# ESP32_with_USBC.net
KiCad netlist of a schematic drawn in Altium Designer
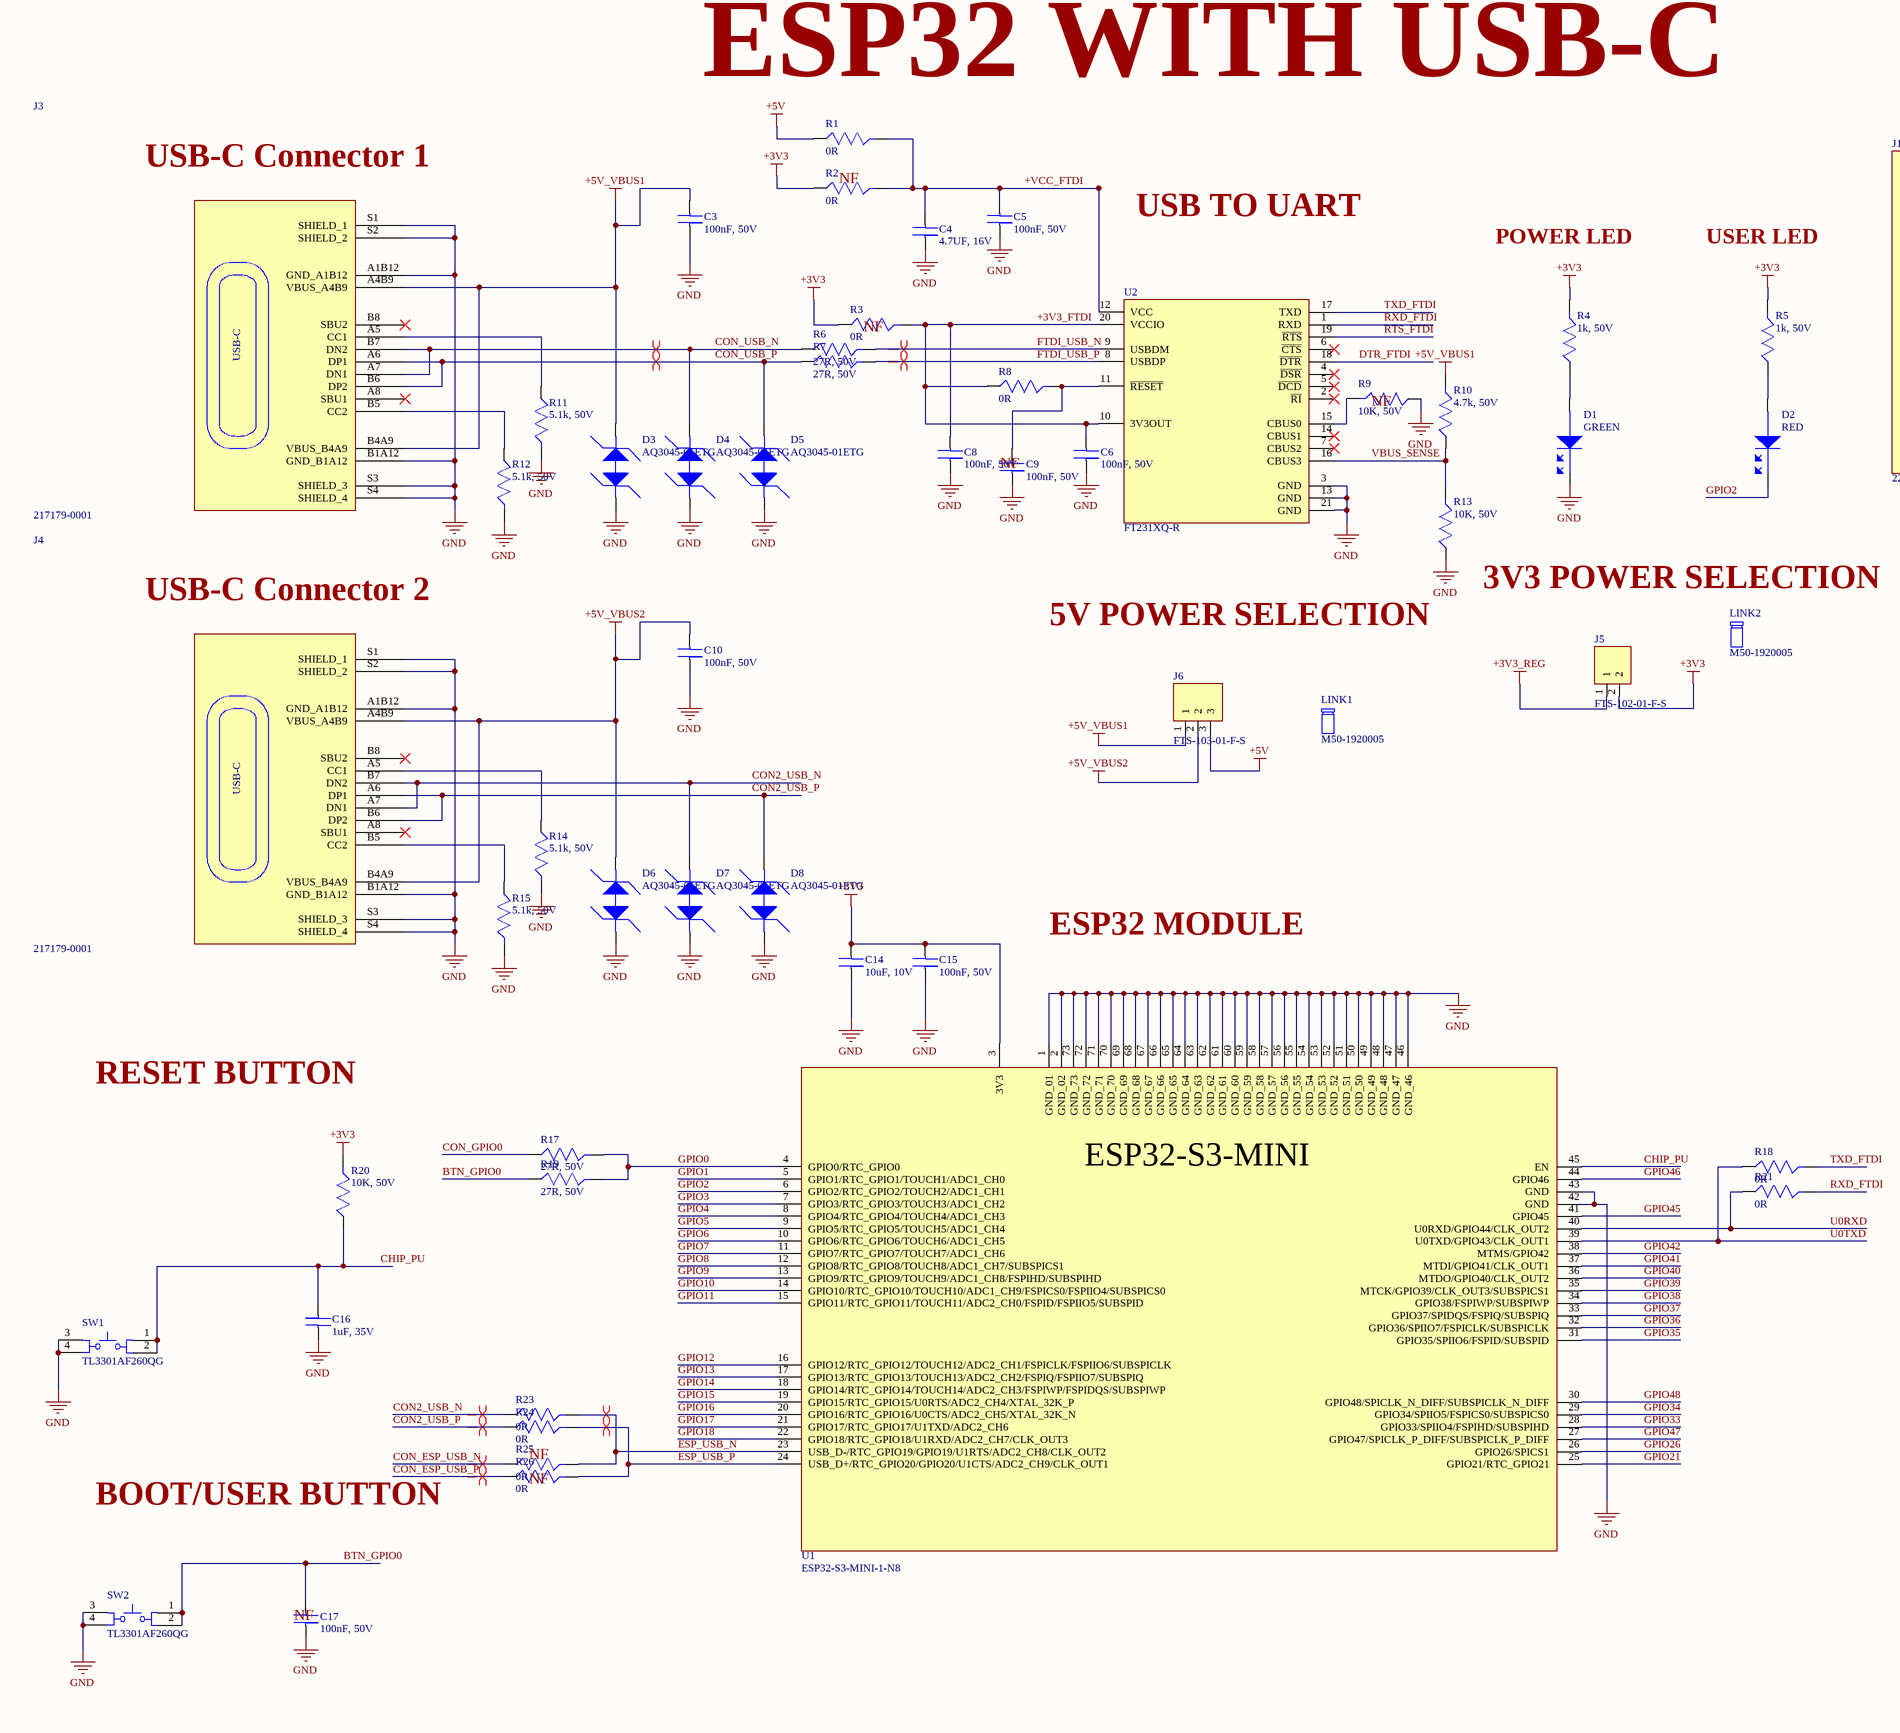
[diagram p0: ESP32 with USBC.SchDoc, left]
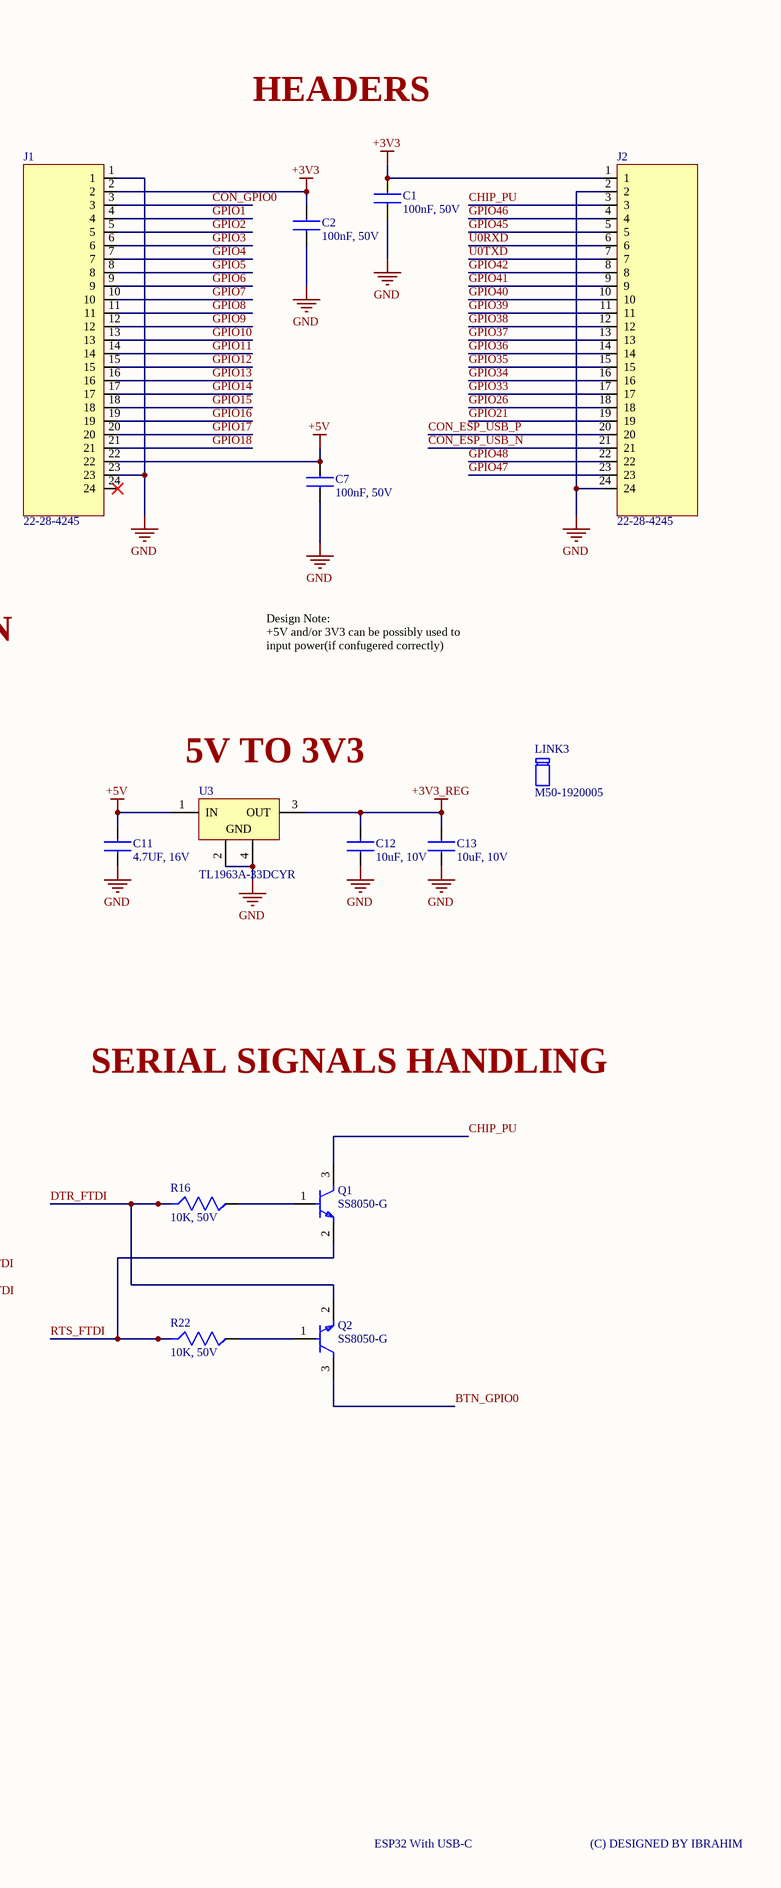
[diagram p1: ESP32 with USBC.SchDoc, right]

(export (version "E")
  (design (tool "Eeschema 10.0.6"))
  (components
    (comp (ref "C1")
      (value "100nF, 50V")
      (footprint "CAPC1005X65N")
      (description "CAP CER 0.1UF 50V X7R 0402")
      (fields
        (field (name "MANUFACTURER") "Samsung Electro-Mechanics")
        (field (name "MANUFACTURER PART NUMBER") "CL05B104KB54PNC")
      )
      (libsource (lib "Schlib") (part "CL05B104KB54PNC"))
    )
    (comp (ref "C2")
      (value "100nF, 50V")
      (footprint "CAPC1005X65N")
      (description "CAP CER 0.1UF 50V X7R 0402")
      (fields
        (field (name "MANUFACTURER") "Samsung Electro-Mechanics")
        (field (name "MANUFACTURER PART NUMBER") "CL05B104KB54PNC")
      )
      (libsource (lib "Schlib") (part "CL05B104KB54PNC"))
    )
    (comp (ref "C3")
      (value "100nF, 50V")
      (footprint "CAPC1005X65N")
      (description "CAP CER 0.1UF 50V X7R 0402")
      (fields
        (field (name "MANUFACTURER") "Samsung Electro-Mechanics")
        (field (name "MANUFACTURER PART NUMBER") "CL05B104KB54PNC")
      )
      (libsource (lib "Schlib") (part "CL05B104KB54PNC"))
    )
    (comp (ref "C4")
      (value "4.7UF, 16V")
      (footprint "CAPC1005X65N")
      (description "CAP CER 4.7UF 16V X5R 0402")
      (fields (field (name "TOLERANCE") "20%") (field (name "LCSC PART NUMBER") "C318563"))
      (libsource (lib "Schlib") (part "CMP-13271-001468-1"))
    )
    (comp (ref "C5")
      (value "100nF, 50V")
      (footprint "CAPC1005X65N")
      (description "CAP CER 0.1UF 50V X7R 0402")
      (fields
        (field (name "MANUFACTURER") "Samsung Electro-Mechanics")
        (field (name "MANUFACTURER PART NUMBER") "CL05B104KB54PNC")
      )
      (libsource (lib "Schlib") (part "CL05B104KB54PNC"))
    )
    (comp (ref "C6")
      (value "100nF, 50V")
      (footprint "CAPC1005X65N")
      (description "CAP CER 0.1UF 50V X7R 0402")
      (fields
        (field (name "MANUFACTURER") "Samsung Electro-Mechanics")
        (field (name "MANUFACTURER PART NUMBER") "CL05B104KB54PNC")
      )
      (libsource (lib "Schlib") (part "CL05B104KB54PNC"))
    )
    (comp (ref "C7")
      (value "100nF, 50V")
      (footprint "CAPC1005X65N")
      (description "CAP CER 0.1UF 50V X7R 0402")
      (fields
        (field (name "MANUFACTURER") "Samsung Electro-Mechanics")
        (field (name "MANUFACTURER PART NUMBER") "CL05B104KB54PNC")
      )
      (libsource (lib "Schlib") (part "CL05B104KB54PNC"))
    )
    (comp (ref "C8")
      (value "100nF, 50V")
      (footprint "CAPC1005X65N")
      (description "CAP CER 0.1UF 50V X7R 0402")
      (fields
        (field (name "MANUFACTURER") "Samsung Electro-Mechanics")
        (field (name "MANUFACTURER PART NUMBER") "CL05B104KB54PNC")
      )
      (libsource (lib "Schlib") (part "CL05B104KB54PNC"))
    )
    (comp (ref "C9")
      (value "100nF, 50V")
      (footprint "CAPC1005X65N")
      (description "CAP CER 0.1UF 50V X7R 0402")
      (fields
        (field (name "MANUFACTURER") "Samsung Electro-Mechanics")
        (field (name "MANUFACTURER PART NUMBER") "CL05B104KB54PNC")
      )
      (libsource (lib "Schlib") (part "CL05B104KB54PNC"))
    )
    (comp (ref "C10")
      (value "100nF, 50V")
      (footprint "CAPC1005X65N")
      (description "CAP CER 0.1UF 50V X7R 0402")
      (fields
        (field (name "MANUFACTURER") "Samsung Electro-Mechanics")
        (field (name "MANUFACTURER PART NUMBER") "CL05B104KB54PNC")
      )
      (libsource (lib "Schlib") (part "CL05B104KB54PNC"))
    )
    (comp (ref "C11")
      (value "4.7UF, 16V")
      (footprint "CAPC1005X65N")
      (description "CAP CER 4.7UF 16V X5R 0402")
      (fields (field (name "TOLERANCE") "20%") (field (name "LCSC PART NUMBER") "C318563"))
      (libsource (lib "Schlib") (part "CMP-13271-001468-1"))
    )
    (comp (ref "C12")
      (value "10uF, 10V")
      (footprint "CAPC1005X65N")
      (description "CAP CER 10UF 10V X5R 0402")
      (fields
        (field (name "MANUFACTURER") "Samsung Electro-Mechanics")
        (field (name "MANUFACTURER PART NUMBER") "CL05A106MP8NUB8")
      )
      (libsource (lib "Schlib") (part "CL05A106MP8NUB8"))
    )
    (comp (ref "C13")
      (value "10uF, 10V")
      (footprint "CAPC1005X65N")
      (description "CAP CER 10UF 10V X5R 0402")
      (fields
        (field (name "MANUFACTURER") "Samsung Electro-Mechanics")
        (field (name "MANUFACTURER PART NUMBER") "CL05A106MP8NUB8")
      )
      (libsource (lib "Schlib") (part "CL05A106MP8NUB8"))
    )
    (comp (ref "C14")
      (value "10uF, 10V")
      (footprint "CAPC1005X65N")
      (description "CAP CER 10UF 10V X5R 0402")
      (fields
        (field (name "MANUFACTURER") "Samsung Electro-Mechanics")
        (field (name "MANUFACTURER PART NUMBER") "CL05A106MP8NUB8")
      )
      (libsource (lib "Schlib") (part "CL05A106MP8NUB8"))
    )
    (comp (ref "C15")
      (value "100nF, 50V")
      (footprint "CAPC1005X65N")
      (description "CAP CER 0.1UF 50V X7R 0402")
      (fields
        (field (name "MANUFACTURER") "Samsung Electro-Mechanics")
        (field (name "MANUFACTURER PART NUMBER") "CL05B104KB54PNC")
      )
      (libsource (lib "Schlib") (part "CL05B104KB54PNC"))
    )
    (comp (ref "C16")
      (value "1uF, 35V")
      (footprint "CAPC1005X65N")
      (description "CAP CER 1UF 35V X5R 0402")
      (fields
        (field (name "MANUFACTURER") "Samsung Electro-Mechanics")
        (field (name "MANUFACTURER PART NUMBER") "CL05A105KL5NRNC")
      )
      (libsource (lib "Schlib") (part "CL05A105KL5NRNC"))
    )
    (comp (ref "C17")
      (value "100nF, 50V")
      (footprint "CAPC1005X65N")
      (description "CAP CER 0.1UF 50V X7R 0402")
      (fields
        (field (name "MANUFACTURER") "Samsung Electro-Mechanics")
        (field (name "MANUFACTURER PART NUMBER") "CL05B104KB54PNC")
      )
      (libsource (lib "Schlib") (part "CL05B104KB54PNC"))
    )
    (comp (ref "D1")
      (value "GREEN")
      (footprint "LED0402G")
      (description "LED YLW-GRN 0402 SMD")
      (fields
        (field (name "MANUFACTURER") "Vishay")
        (field (name "MANUFACTURER PART NUMBER") "VLMG1500-GS08")
      )
      (libsource (lib "Schlib") (part "VLMG1500-GS08"))
    )
    (comp (ref "D2")
      (value "RED")
      (footprint "LED0402R")
      (description "LED RED 0402 SMD")
      (fields
        (field (name "MANUFACTURER") "Vishay")
        (field (name "MANUFACTURER PART NUMBER") "VLMS1500-GS08")
      )
      (libsource (lib "Schlib") (part "VLMS1500-GS08"))
    )
    (comp (ref "D3")
      (value "AQ3045-01ETG")
      (footprint "SOD882")
      (description "TVS DIODE 5.3VWM 12VC SOD882")
      (fields (field (name "MANUFACTURER") "Littelfuse") (field (name "LCSC PART NUMBER") "C3710326"))
      (libsource (lib "Schlib") (part "AQ3045-01ETG"))
    )
    (comp (ref "D4")
      (value "AQ3045-01ETG")
      (footprint "SOD882")
      (description "TVS DIODE 5.3VWM 12VC SOD882")
      (fields (field (name "MANUFACTURER") "Littelfuse") (field (name "LCSC PART NUMBER") "C3710326"))
      (libsource (lib "Schlib") (part "AQ3045-01ETG"))
    )
    (comp (ref "D5")
      (value "AQ3045-01ETG")
      (footprint "SOD882")
      (description "TVS DIODE 5.3VWM 12VC SOD882")
      (fields (field (name "MANUFACTURER") "Littelfuse") (field (name "LCSC PART NUMBER") "C3710326"))
      (libsource (lib "Schlib") (part "AQ3045-01ETG"))
    )
    (comp (ref "D6")
      (value "AQ3045-01ETG")
      (footprint "SOD882")
      (description "TVS DIODE 5.3VWM 12VC SOD882")
      (fields (field (name "MANUFACTURER") "Littelfuse") (field (name "LCSC PART NUMBER") "C3710326"))
      (libsource (lib "Schlib") (part "AQ3045-01ETG"))
    )
    (comp (ref "D7")
      (value "AQ3045-01ETG")
      (footprint "SOD882")
      (description "TVS DIODE 5.3VWM 12VC SOD882")
      (fields (field (name "MANUFACTURER") "Littelfuse") (field (name "LCSC PART NUMBER") "C3710326"))
      (libsource (lib "Schlib") (part "AQ3045-01ETG"))
    )
    (comp (ref "D8")
      (value "AQ3045-01ETG")
      (footprint "SOD882")
      (description "TVS DIODE 5.3VWM 12VC SOD882")
      (fields (field (name "MANUFACTURER") "Littelfuse") (field (name "LCSC PART NUMBER") "C3710326"))
      (libsource (lib "Schlib") (part "AQ3045-01ETG"))
    )
    (comp (ref "J1")
      (value "22-28-4245")
      (footprint "HDR_1X24_2.54MM")
      (description "Conn Unshrouded Header HDR 24 POS 2.54mm Solder ST Thru-Hole KK® Bag")
      (fields (field (name "MANUFACTURER") "Molex") (field (name "LCSC PART NUMBER") "C7145888"))
      (libsource (lib "Schlib") (part "22-28-4245"))
    )
    (comp (ref "J2")
      (value "22-28-4245")
      (footprint "HDR_1X24_2.54MM")
      (description "Conn Unshrouded Header HDR 24 POS 2.54mm Solder ST Thru-Hole KK® Bag")
      (fields (field (name "MANUFACTURER") "Molex") (field (name "LCSC PART NUMBER") "C7145888"))
      (libsource (lib "") (part "22-28-4245_1"))
    )
    (comp (ref "J3")
      (value "217179-0001")
      (footprint "FP-2171790001-MFG")
      (description "CONN RCP USB2.0 TYP C 24P SMD RA")
      (fields (field (name "MANUFACTURER") "Molex") (field (name "LCSC PART NUMBER") "C3197684"))
      (libsource (lib "Schlib") (part "217179-0001"))
    )
    (comp (ref "J4")
      (value "217179-0001")
      (footprint "FP-2171790001-MFG")
      (description "CONN RCP USB2.0 TYP C 24P SMD RA")
      (fields (field (name "MANUFACTURER") "Molex") (field (name "LCSC PART NUMBER") "C3197684"))
      (libsource (lib "Schlib") (part "217179-0001"))
    )
    (comp (ref "J5")
      (value "FTS-102-01-F-S")
      (footprint "HDR_1X2_1.27MM")
      (description "CONN HEADER VERT 2POS 1.27MM")
      (fields (field (name "MANUFACTURER") "Samtec") (field (name "LCSC PART NUMBER") "C6045317"))
      (libsource (lib "Schlib") (part "FTS-102-01-F-S"))
    )
    (comp (ref "J6")
      (value "FTS-103-01-F-S")
      (footprint "HDR_1X3_1.27MM")
      (description "CONN HEADER VERT 3POS 1.27MM")
      (fields (field (name "MANUFACTURER") "Samtec") (field (name "LCSC PART NUMBER") "C3333578"))
      (libsource (lib "Schlib") (part "FTS-103-01-F-S"))
    )
    (comp (ref "LINK1")
      (value "M50-1920005")
      (description "CONN SHUNT 1.27MM RED")
      (fields (field (name "MANUFACTURER") "Harwin") (field (name "LCSC PART NUMBER") "C6985646"))
      (libsource (lib "Schlib") (part "M50-1920005"))
    )
    (comp (ref "LINK2")
      (value "M50-1920005")
      (description "CONN SHUNT 1.27MM RED")
      (fields (field (name "MANUFACTURER") "Harwin") (field (name "LCSC PART NUMBER") "C6985646"))
      (libsource (lib "Schlib") (part "M50-1920005"))
    )
    (comp (ref "LINK3")
      (value "M50-1920005")
      (description "CONN SHUNT 1.27MM RED")
      (fields (field (name "MANUFACTURER") "Harwin") (field (name "LCSC PART NUMBER") "C6985646"))
      (libsource (lib "Schlib") (part "M50-1920005"))
    )
    (comp (ref "Q1")
      (value "SS8050-G")
      (footprint "FP-SS8050-G-IPC_B")
      (description "TRANS NPN 25V 1.5A SOT-23-3")
      (fields (field (name "MANUFACTURER") "Comchip") (field (name "LCSC PART NUMBER") "C3199946"))
      (libsource (lib "Schlib") (part "SS8050-G"))
    )
    (comp (ref "Q2")
      (value "SS8050-G")
      (footprint "FP-SS8050-G-IPC_B")
      (description "TRANS NPN 25V 1.5A SOT-23-3")
      (fields (field (name "MANUFACTURER") "Comchip") (field (name "LCSC PART NUMBER") "C3199946"))
      (libsource (lib "Schlib") (part "SS8050-G"))
    )
    (comp (ref "R1")
      (value "0R")
      (footprint "RESC1005X37N")
      (description "RES 0 OHM JUMPER 1/16W 0402")
      (fields
        (field (name "MANUFACTURER") "Yageo Group")
        (field (name "MANUFACTURER PART NUMBER") "RC0402JR-070RL")
      )
      (libsource (lib "Schlib") (part "RC0402JR-070RL"))
    )
    (comp (ref "R2")
      (value "0R")
      (footprint "RESC1005X37N")
      (description "RES 0 OHM JUMPER 1/16W 0402")
      (fields
        (field (name "MANUFACTURER") "Yageo Group")
        (field (name "MANUFACTURER PART NUMBER") "RC0402JR-070RL")
      )
      (libsource (lib "Schlib") (part "RC0402JR-070RL"))
    )
    (comp (ref "R3")
      (value "0R")
      (footprint "RESC1005X37N")
      (description "RES 0 OHM JUMPER 1/16W 0402")
      (fields
        (field (name "MANUFACTURER") "Yageo Group")
        (field (name "MANUFACTURER PART NUMBER") "RC0402JR-070RL")
      )
      (libsource (lib "Schlib") (part "RC0402JR-070RL"))
    )
    (comp (ref "R4")
      (value "1k, 50V")
      (footprint "RESC1005X37N")
      (description "RES 1K OHM 1% 1/16W 0402")
      (fields
        (field (name "MANUFACTURER") "Yageo Group")
        (field (name "MANUFACTURER PART NUMBER") "RC0402FR-071KL")
      )
      (libsource (lib "Schlib") (part "RC0402FR-071KL"))
    )
    (comp (ref "R5")
      (value "1k, 50V")
      (footprint "RESC1005X37N")
      (description "RES 1K OHM 1% 1/16W 0402")
      (fields
        (field (name "MANUFACTURER") "Yageo Group")
        (field (name "MANUFACTURER PART NUMBER") "RC0402FR-071KL")
      )
      (libsource (lib "Schlib") (part "RC0402FR-071KL"))
    )
    (comp (ref "R6")
      (value "27R, 50V")
      (footprint "RESC1005X37N")
      (description "RES 27 OHM 1% 1/16W 0402")
      (fields
        (field (name "MANUFACTURER") "Yageo Group")
        (field (name "MANUFACTURER PART NUMBER") "RC0402FR-0727RL")
      )
      (libsource (lib "Schlib") (part "RC0402FR-0727RL"))
    )
    (comp (ref "R7")
      (value "27R, 50V")
      (footprint "RESC1005X37N")
      (description "RES 27 OHM 1% 1/16W 0402")
      (fields
        (field (name "MANUFACTURER") "Yageo Group")
        (field (name "MANUFACTURER PART NUMBER") "RC0402FR-0727RL")
      )
      (libsource (lib "Schlib") (part "RC0402FR-0727RL"))
    )
    (comp (ref "R8")
      (value "0R")
      (footprint "RESC1005X37N")
      (description "RES 0 OHM JUMPER 1/16W 0402")
      (fields
        (field (name "MANUFACTURER") "Yageo Group")
        (field (name "MANUFACTURER PART NUMBER") "RC0402JR-070RL")
      )
      (libsource (lib "Schlib") (part "RC0402JR-070RL"))
    )
    (comp (ref "R9")
      (value "10K, 50V")
      (footprint "RESC1005X37N")
      (description "RES SMD 10K OHM 1% 1/16W 0402")
      (fields
        (field (name "MANUFACTURER") "Yageo Group")
        (field (name "MANUFACTURER PART NUMBER") "AC0402FR-0710KL")
      )
      (libsource (lib "Schlib") (part "AC0402FR-0710KL"))
    )
    (comp (ref "R10")
      (value "4.7k, 50V")
      (footprint "RESC1005X37N")
      (description "RES 4.7K OHM 1% 1/16W 0402")
      (fields
        (field (name "MANUFACTURER") "Yageo Group")
        (field (name "MANUFACTURER PART NUMBER") "RC0402FR-074K7L")
      )
      (libsource (lib "Schlib") (part "RC0402FR-074K7L"))
    )
    (comp (ref "R11")
      (value "5.1k, 50V")
      (footprint "RESC1005X37N")
      (description "Res Thick Film 0402 5.1K Ohm 1% 0.063W(1/16W) ±100ppm/C Pad SMD Automotive T/R")
      (fields
        (field (name "MANUFACTURER") "Yageo Group")
        (field (name "MANUFACTURER PART NUMBER") "AC0402FR-075K1L")
      )
      (libsource (lib "Schlib") (part "AC0402FR-075K1L"))
    )
    (comp (ref "R12")
      (value "5.1k, 50V")
      (footprint "RESC1005X37N")
      (description "Res Thick Film 0402 5.1K Ohm 1% 0.063W(1/16W) ±100ppm/C Pad SMD Automotive T/R")
      (fields
        (field (name "MANUFACTURER") "Yageo Group")
        (field (name "MANUFACTURER PART NUMBER") "AC0402FR-075K1L")
      )
      (libsource (lib "Schlib") (part "AC0402FR-075K1L"))
    )
    (comp (ref "R13")
      (value "10K, 50V")
      (footprint "RESC1005X37N")
      (description "RES SMD 10K OHM 1% 1/16W 0402")
      (fields
        (field (name "MANUFACTURER") "Yageo Group")
        (field (name "MANUFACTURER PART NUMBER") "AC0402FR-0710KL")
      )
      (libsource (lib "Schlib") (part "AC0402FR-0710KL"))
    )
    (comp (ref "R14")
      (value "5.1k, 50V")
      (footprint "RESC1005X37N")
      (description "Res Thick Film 0402 5.1K Ohm 1% 0.063W(1/16W) ±100ppm/C Pad SMD Automotive T/R")
      (fields
        (field (name "MANUFACTURER") "Yageo Group")
        (field (name "MANUFACTURER PART NUMBER") "AC0402FR-075K1L")
      )
      (libsource (lib "Schlib") (part "AC0402FR-075K1L"))
    )
    (comp (ref "R15")
      (value "5.1k, 50V")
      (footprint "RESC1005X37N")
      (description "Res Thick Film 0402 5.1K Ohm 1% 0.063W(1/16W) ±100ppm/C Pad SMD Automotive T/R")
      (fields
        (field (name "MANUFACTURER") "Yageo Group")
        (field (name "MANUFACTURER PART NUMBER") "AC0402FR-075K1L")
      )
      (libsource (lib "Schlib") (part "AC0402FR-075K1L"))
    )
    (comp (ref "R16")
      (value "10K, 50V")
      (footprint "RESC1005X37N")
      (description "RES SMD 10K OHM 1% 1/16W 0402")
      (fields
        (field (name "MANUFACTURER") "Yageo Group")
        (field (name "MANUFACTURER PART NUMBER") "AC0402FR-0710KL")
      )
      (libsource (lib "Schlib") (part "AC0402FR-0710KL"))
    )
    (comp (ref "R17")
      (value "27R, 50V")
      (footprint "RESC1005X37N")
      (description "RES 27 OHM 1% 1/16W 0402")
      (fields
        (field (name "MANUFACTURER") "Yageo Group")
        (field (name "MANUFACTURER PART NUMBER") "RC0402FR-0727RL")
      )
      (libsource (lib "Schlib") (part "RC0402FR-0727RL"))
    )
    (comp (ref "R18")
      (value "0R")
      (footprint "RESC1005X37N")
      (description "RES 0 OHM JUMPER 1/16W 0402")
      (fields
        (field (name "MANUFACTURER") "Yageo Group")
        (field (name "MANUFACTURER PART NUMBER") "RC0402JR-070RL")
      )
      (libsource (lib "Schlib") (part "RC0402JR-070RL"))
    )
    (comp (ref "R19")
      (value "27R, 50V")
      (footprint "RESC1005X37N")
      (description "RES 27 OHM 1% 1/16W 0402")
      (fields
        (field (name "MANUFACTURER") "Yageo Group")
        (field (name "MANUFACTURER PART NUMBER") "RC0402FR-0727RL")
      )
      (libsource (lib "Schlib") (part "RC0402FR-0727RL"))
    )
    (comp (ref "R20")
      (value "10K, 50V")
      (footprint "RESC1005X37N")
      (description "RES SMD 10K OHM 1% 1/16W 0402")
      (fields
        (field (name "MANUFACTURER") "Yageo Group")
        (field (name "MANUFACTURER PART NUMBER") "AC0402FR-0710KL")
      )
      (libsource (lib "Schlib") (part "AC0402FR-0710KL"))
    )
    (comp (ref "R21")
      (value "0R")
      (footprint "RESC1005X37N")
      (description "RES 0 OHM JUMPER 1/16W 0402")
      (fields
        (field (name "MANUFACTURER") "Yageo Group")
        (field (name "MANUFACTURER PART NUMBER") "RC0402JR-070RL")
      )
      (libsource (lib "Schlib") (part "RC0402JR-070RL"))
    )
    (comp (ref "R22")
      (value "10K, 50V")
      (footprint "RESC1005X37N")
      (description "RES SMD 10K OHM 1% 1/16W 0402")
      (fields
        (field (name "MANUFACTURER") "Yageo Group")
        (field (name "MANUFACTURER PART NUMBER") "AC0402FR-0710KL")
      )
      (libsource (lib "Schlib") (part "AC0402FR-0710KL"))
    )
    (comp (ref "R23")
      (value "0R")
      (footprint "RESC1005X37N")
      (description "RES 0 OHM JUMPER 1/16W 0402")
      (fields
        (field (name "MANUFACTURER") "Yageo Group")
        (field (name "MANUFACTURER PART NUMBER") "RC0402JR-070RL")
      )
      (libsource (lib "Schlib") (part "RC0402JR-070RL"))
    )
    (comp (ref "R24")
      (value "0R")
      (footprint "RESC1005X37N")
      (description "RES 0 OHM JUMPER 1/16W 0402")
      (fields
        (field (name "MANUFACTURER") "Yageo Group")
        (field (name "MANUFACTURER PART NUMBER") "RC0402JR-070RL")
      )
      (libsource (lib "Schlib") (part "RC0402JR-070RL"))
    )
    (comp (ref "R25")
      (value "0R")
      (footprint "RESC1005X37N")
      (description "RES 0 OHM JUMPER 1/16W 0402")
      (fields
        (field (name "MANUFACTURER") "Yageo Group")
        (field (name "MANUFACTURER PART NUMBER") "RC0402JR-070RL")
      )
      (libsource (lib "Schlib") (part "RC0402JR-070RL"))
    )
    (comp (ref "R26")
      (value "0R")
      (footprint "RESC1005X37N")
      (description "RES 0 OHM JUMPER 1/16W 0402")
      (fields
        (field (name "MANUFACTURER") "Yageo Group")
        (field (name "MANUFACTURER PART NUMBER") "RC0402JR-070RL")
      )
      (libsource (lib "Schlib") (part "RC0402JR-070RL"))
    )
    (comp (ref "SW1")
      (value "TL3301AF260QG")
      (footprint "ESWI-TL3301AF260QG_V")
      (description "Switch Tactile N.O. SPST Round Button Gull Wing 0.05A 12VDC 100000Cycles 2.55N SMD T/R")
      (fields (field (name "MANUFACTURER") "E-Switch"))
      (libsource (lib "Schlib") (part "TL3301AF260QG"))
    )
    (comp (ref "SW2")
      (value "TL3301AF260QG")
      (footprint "ESWI-TL3301AF260QG_V")
      (description "Switch Tactile N.O. SPST Round Button Gull Wing 0.05A 12VDC 100000Cycles 2.55N SMD T/R")
      (fields (field (name "MANUFACTURER") "E-Switch"))
      (libsource (lib "Schlib") (part "TL3301AF260QG"))
    )
    (comp (ref "U1")
      (value "ESP32-S3-MINI-1-N8")
      (footprint "XCVR_ESP32-S3-MINI-1-N8")
      (description "20.5dBm ESP32-S3FN8 Chip 2.4GHz SMD WiFi Modules ROHS")
      (fields (field (name "MANUFACTURER") "Espressif Systems") (field (name "LCSC PART NUMBER") "C2913206"))
      (libsource (lib "Schlib") (part "ESP32-S3-MINI-1-N8"))
    )
    (comp (ref "U2")
      (value "FT231XQ-R")
      (footprint "FP-QFN-20-IPC_B")
      (description "IC USB SERIAL FULL UART 20QFN")
      (fields (field (name "MANUFACTURER") "FTDI") (field (name "LCSC PART NUMBER") "C132159"))
      (libsource (lib "Schlib") (part "FT231XQ-R"))
    )
    (comp (ref "U3")
      (value "TL1963A-33DCYR")
      (footprint "DCY0004A_N")
      (description "IC REG LIN 3.3V 1.5A SOT-223-4")
      (fields (field (name "MANUFACTURER") "Texas Instruments") (field (name "LCSC PART NUMBER") "C181262"))
      (libsource (lib "Schlib") (part "TL1963A-33DCYR"))
    )
  )
  (nets
    (net (code "1") (name "+3V3") (class "Default")
      (node (ref "C1") (pin "1") (pinfunction "1_1") (pintype "passive"))
      (node (ref "C14") (pin "1") (pinfunction "1_1") (pintype "passive"))
      (node (ref "C15") (pin "1") (pinfunction "1_1") (pintype "passive"))
      (node (ref "C2") (pin "1") (pinfunction "1_1") (pintype "passive"))
      (node (ref "J1") (pin "2") (pinfunction "2_2") (pintype "passive"))
      (node (ref "J2") (pin "1") (pinfunction "1_1") (pintype "passive"))
      (node (ref "J5") (pin "2") (pinfunction "2_2") (pintype "passive"))
      (node (ref "R2") (pin "1") (pinfunction "1_1") (pintype "passive"))
      (node (ref "R20") (pin "2") (pinfunction "2_2") (pintype "passive"))
      (node (ref "R3") (pin "1") (pinfunction "1_1") (pintype "passive"))
      (node (ref "R4") (pin "2") (pinfunction "2_2") (pintype "passive"))
      (node (ref "R5") (pin "2") (pinfunction "2_2") (pintype "passive"))
      (node (ref "U1") (pin "3") (pinfunction "3V3_3") (pintype "passive"))
    )
    (net (code "2") (name "+3V3_REG") (class "Default")
      (node (ref "C12") (pin "1") (pinfunction "1_1") (pintype "passive"))
      (node (ref "C13") (pin "1") (pinfunction "1_1") (pintype "passive"))
      (node (ref "J5") (pin "1") (pinfunction "1_1") (pintype "passive"))
      (node (ref "U3") (pin "3") (pinfunction "OUT_3") (pintype "power_in"))
    )
    (net (code "3") (name "+5V") (class "Default")
      (node (ref "C11") (pin "1") (pinfunction "1_1") (pintype "passive"))
      (node (ref "C7") (pin "1") (pinfunction "1_1") (pintype "passive"))
      (node (ref "J1") (pin "22") (pinfunction "22_22") (pintype "passive"))
      (node (ref "J6") (pin "3") (pinfunction "3_3") (pintype "passive"))
      (node (ref "R1") (pin "1") (pinfunction "1_1") (pintype "passive"))
      (node (ref "U3") (pin "1") (pinfunction "IN_1") (pintype "power_in"))
    )
    (net (code "4") (name "+5V_VBUS1") (class "Default")
      (node (ref "C3") (pin "1") (pinfunction "1_1") (pintype "passive"))
      (node (ref "D3") (pin "2") (pinfunction "2_2") (pintype "passive"))
      (node (ref "J3") (pin "A4B9") (pinfunction "VBUS_A4B9_A4B9") (pintype "passive"))
      (node (ref "J3") (pin "B4A9") (pinfunction "VBUS_B4A9_B4A9") (pintype "passive"))
      (node (ref "J6") (pin "1") (pinfunction "1_1") (pintype "passive"))
      (node (ref "R10") (pin "2") (pinfunction "2_2") (pintype "passive"))
    )
    (net (code "5") (name "+5V_VBUS2") (class "Default")
      (node (ref "C10") (pin "1") (pinfunction "1_1") (pintype "passive"))
      (node (ref "D6") (pin "2") (pinfunction "2_2") (pintype "passive"))
      (node (ref "J4") (pin "A4B9") (pinfunction "VBUS_A4B9_A4B9") (pintype "passive"))
      (node (ref "J4") (pin "B4A9") (pinfunction "VBUS_B4A9_B4A9") (pintype "passive"))
      (node (ref "J6") (pin "2") (pinfunction "2_2") (pintype "passive"))
    )
    (net (code "6") (name "/+3V3_FTDI") (class "Default")
      (node (ref "C6") (pin "1") (pinfunction "1_1") (pintype "passive"))
      (node (ref "C8") (pin "1") (pinfunction "1_1") (pintype "passive"))
      (node (ref "R3") (pin "2") (pinfunction "2_2") (pintype "passive"))
      (node (ref "R8") (pin "1") (pinfunction "1_1") (pintype "passive"))
      (node (ref "U2") (pin "10") (pinfunction "3V3OUT_10") (pintype "passive"))
      (node (ref "U2") (pin "20") (pinfunction "VCCIO_20") (pintype "passive"))
    )
    (net (code "7") (name "/+VCC_FTDI") (class "Default")
      (node (ref "C4") (pin "1") (pinfunction "1_1") (pintype "passive"))
      (node (ref "C5") (pin "1") (pinfunction "1_1") (pintype "passive"))
      (node (ref "R1") (pin "2") (pinfunction "2_2") (pintype "passive"))
      (node (ref "R2") (pin "2") (pinfunction "2_2") (pintype "passive"))
      (node (ref "U2") (pin "12") (pinfunction "VCC_12") (pintype "passive"))
    )
    (net (code "8") (name "/BTN_GPIO0") (class "Default")
      (node (ref "C17") (pin "1") (pinfunction "1_1") (pintype "passive"))
      (node (ref "Q2") (pin "3") (pinfunction "C_3") (pintype "passive"))
      (node (ref "R19") (pin "1") (pinfunction "1_1") (pintype "passive"))
      (node (ref "SW2") (pin "1") (pinfunction "1_1") (pintype "passive"))
      (node (ref "SW2") (pin "2") (pinfunction "2_2") (pintype "passive"))
    )
    (net (code "9") (name "/CHIP_PU") (class "Default")
      (node (ref "C16") (pin "2") (pinfunction "2_2") (pintype "passive"))
      (node (ref "J2") (pin "3") (pinfunction "3_3") (pintype "passive"))
      (node (ref "Q1") (pin "3") (pinfunction "C_3") (pintype "passive"))
      (node (ref "R20") (pin "1") (pinfunction "1_1") (pintype "passive"))
      (node (ref "SW1") (pin "1") (pinfunction "1_1") (pintype "passive"))
      (node (ref "SW1") (pin "2") (pinfunction "2_2") (pintype "passive"))
      (node (ref "U1") (pin "45") (pinfunction "EN_45") (pintype "passive"))
    )
    (net (code "10") (name "/CON2_USB_N") (class "Default")
      (node (ref "D7") (pin "2") (pinfunction "2_2") (pintype "passive"))
      (node (ref "J4") (pin "A7") (pinfunction "DN1_A7") (pintype "passive"))
      (node (ref "J4") (pin "B7") (pinfunction "DN2_B7") (pintype "passive"))
      (node (ref "R23") (pin "1") (pinfunction "1_1") (pintype "passive"))
    )
    (net (code "11") (name "/CON2_USB_P") (class "Default")
      (node (ref "D8") (pin "2") (pinfunction "2_2") (pintype "passive"))
      (node (ref "J4") (pin "A6") (pinfunction "DP1_A6") (pintype "passive"))
      (node (ref "J4") (pin "B6") (pinfunction "DP2_B6") (pintype "passive"))
      (node (ref "R24") (pin "1") (pinfunction "1_1") (pintype "passive"))
    )
    (net (code "12") (name "/CON_ESP_USB_N") (class "Default")
      (node (ref "J2") (pin "21") (pinfunction "21_21") (pintype "passive"))
      (node (ref "R25") (pin "1") (pinfunction "1_1") (pintype "passive"))
    )
    (net (code "13") (name "/CON_ESP_USB_P") (class "Default")
      (node (ref "J2") (pin "20") (pinfunction "20_20") (pintype "passive"))
      (node (ref "R26") (pin "1") (pinfunction "1_1") (pintype "passive"))
    )
    (net (code "14") (name "/CON_GPIO0") (class "Default")
      (node (ref "J1") (pin "3") (pinfunction "3_3") (pintype "passive"))
      (node (ref "R17") (pin "1") (pinfunction "1_1") (pintype "passive"))
    )
    (net (code "15") (name "/CON_USB_N") (class "Default")
      (node (ref "D4") (pin "2") (pinfunction "2_2") (pintype "passive"))
      (node (ref "J3") (pin "A7") (pinfunction "DN1_A7") (pintype "passive"))
      (node (ref "J3") (pin "B7") (pinfunction "DN2_B7") (pintype "passive"))
      (node (ref "R6") (pin "1") (pinfunction "1_1") (pintype "passive"))
    )
    (net (code "16") (name "/CON_USB_P") (class "Default")
      (node (ref "D5") (pin "2") (pinfunction "2_2") (pintype "passive"))
      (node (ref "J3") (pin "A6") (pinfunction "DP1_A6") (pintype "passive"))
      (node (ref "J3") (pin "B6") (pinfunction "DP2_B6") (pintype "passive"))
      (node (ref "R7") (pin "1") (pinfunction "1_1") (pintype "passive"))
    )
    (net (code "17") (name "/DTR_FTDI") (class "Default")
      (node (ref "Q2") (pin "2") (pinfunction "E_2") (pintype "passive"))
      (node (ref "R16") (pin "2") (pinfunction "2_2") (pintype "passive"))
      (node (ref "U2") (pin "18") (pinfunction "~{DTR}_18") (pintype "passive"))
    )
    (net (code "18") (name "/ESP_USB_N") (class "Default")
      (node (ref "R23") (pin "2") (pinfunction "2_2") (pintype "passive"))
      (node (ref "R25") (pin "2") (pinfunction "2_2") (pintype "passive"))
      (node (ref "U1") (pin "23") (pinfunction "USB_D-/RTC_GPIO19/GPIO19/U1RTS/ADC2_CH8/CLK_OUT2_23") (pintype "passive"))
    )
    (net (code "19") (name "/ESP_USB_P") (class "Default")
      (node (ref "R24") (pin "2") (pinfunction "2_2") (pintype "passive"))
      (node (ref "R26") (pin "2") (pinfunction "2_2") (pintype "passive"))
      (node (ref "U1") (pin "24") (pinfunction "USB_D+/RTC_GPIO20/GPIO20/U1CTS/ADC2_CH9/CLK_OUT1_24") (pintype "passive"))
    )
    (net (code "20") (name "/FTDI_USB_N") (class "Default")
      (node (ref "R6") (pin "2") (pinfunction "2_2") (pintype "passive"))
      (node (ref "U2") (pin "9") (pinfunction "USBDM_9") (pintype "passive"))
    )
    (net (code "21") (name "/FTDI_USB_P") (class "Default")
      (node (ref "R7") (pin "2") (pinfunction "2_2") (pintype "passive"))
      (node (ref "U2") (pin "8") (pinfunction "USBDP_8") (pintype "passive"))
    )
    (net (code "22") (name "/GPIO0") (class "Default")
      (node (ref "R17") (pin "2") (pinfunction "2_2") (pintype "passive"))
      (node (ref "R19") (pin "2") (pinfunction "2_2") (pintype "passive"))
      (node (ref "U1") (pin "4") (pinfunction "GPIO0/RTC_GPIO0_4") (pintype "passive"))
    )
    (net (code "23") (name "/GPIO1") (class "Default")
      (node (ref "J1") (pin "4") (pinfunction "4_4") (pintype "passive"))
      (node (ref "U1") (pin "5") (pinfunction "GPIO1/RTC_GPIO1/TOUCH1/ADC1_CH0_5") (pintype "passive"))
    )
    (net (code "24") (name "/GPIO2") (class "Default")
      (node (ref "D2") (pin "1") (pinfunction "1_1") (pintype "passive"))
      (node (ref "J1") (pin "5") (pinfunction "5_5") (pintype "passive"))
      (node (ref "U1") (pin "6") (pinfunction "GPIO2/RTC_GPIO2/TOUCH2/ADC1_CH1_6") (pintype "passive"))
    )
    (net (code "25") (name "/GPIO3") (class "Default")
      (node (ref "J1") (pin "6") (pinfunction "6_6") (pintype "passive"))
      (node (ref "U1") (pin "7") (pinfunction "GPIO3/RTC_GPIO3/TOUCH3/ADC1_CH2_7") (pintype "passive"))
    )
    (net (code "26") (name "/GPIO4") (class "Default")
      (node (ref "J1") (pin "7") (pinfunction "7_7") (pintype "passive"))
      (node (ref "U1") (pin "8") (pinfunction "GPIO4/RTC_GPIO4/TOUCH4/ADC1_CH3_8") (pintype "passive"))
    )
    (net (code "27") (name "/GPIO5") (class "Default")
      (node (ref "J1") (pin "8") (pinfunction "8_8") (pintype "passive"))
      (node (ref "U1") (pin "9") (pinfunction "GPIO5/RTC_GPIO5/TOUCH5/ADC1_CH4_9") (pintype "passive"))
    )
    (net (code "28") (name "/GPIO6") (class "Default")
      (node (ref "J1") (pin "9") (pinfunction "9_9") (pintype "passive"))
      (node (ref "U1") (pin "10") (pinfunction "GPIO6/RTC_GPIO6/TOUCH6/ADC1_CH5_10") (pintype "passive"))
    )
    (net (code "29") (name "/GPIO7") (class "Default")
      (node (ref "J1") (pin "10") (pinfunction "10_10") (pintype "passive"))
      (node (ref "U1") (pin "11") (pinfunction "GPIO7/RTC_GPIO7/TOUCH7/ADC1_CH6_11") (pintype "passive"))
    )
    (net (code "30") (name "/GPIO8") (class "Default")
      (node (ref "J1") (pin "11") (pinfunction "11_11") (pintype "passive"))
      (node (ref "U1") (pin "12") (pinfunction "GPIO8/RTC_GPIO8/TOUCH8/ADC1_CH7/SUBSPICS1_12") (pintype "passive"))
    )
    (net (code "31") (name "/GPIO9") (class "Default")
      (node (ref "J1") (pin "12") (pinfunction "12_12") (pintype "passive"))
      (node (ref "U1") (pin "13") (pinfunction "GPIO9/RTC_GPIO9/TOUCH9/ADC1_CH8/FSPIHD/SUBSPIHD_13") (pintype "passive"))
    )
    (net (code "32") (name "/GPIO10") (class "Default")
      (node (ref "J1") (pin "13") (pinfunction "13_13") (pintype "passive"))
      (node (ref "U1") (pin "14") (pinfunction "GPIO10/RTC_GPIO10/TOUCH10/ADC1_CH9/FSPICS0/FSPIIO4/SUBSPICS0_14") (pintype "passive"))
    )
    (net (code "33") (name "/GPIO11") (class "Default")
      (node (ref "J1") (pin "14") (pinfunction "14_14") (pintype "passive"))
      (node (ref "U1") (pin "15") (pinfunction "GPIO11/RTC_GPIO11/TOUCH11/ADC2_CH0/FSPID/FSPIIO5/SUBSPID_15") (pintype "passive"))
    )
    (net (code "34") (name "/GPIO12") (class "Default")
      (node (ref "J1") (pin "15") (pinfunction "15_15") (pintype "passive"))
      (node (ref "U1") (pin "16") (pinfunction "GPIO12/RTC_GPIO12/TOUCH12/ADC2_CH1/FSPICLK/FSPIIO6/SUBSPICLK_16") (pintype "passive"))
    )
    (net (code "35") (name "/GPIO13") (class "Default")
      (node (ref "J1") (pin "16") (pinfunction "16_16") (pintype "passive"))
      (node (ref "U1") (pin "17") (pinfunction "GPIO13/RTC_GPIO13/TOUCH13/ADC2_CH2/FSPIQ/FSPIIO7/SUBSPIQ_17") (pintype "passive"))
    )
    (net (code "36") (name "/GPIO14") (class "Default")
      (node (ref "J1") (pin "17") (pinfunction "17_17") (pintype "passive"))
      (node (ref "U1") (pin "18") (pinfunction "GPIO14/RTC_GPIO14/TOUCH14/ADC2_CH3/FSPIWP/FSPIDQS/SUBSPIWP_18") (pintype "passive"))
    )
    (net (code "37") (name "/GPIO15") (class "Default")
      (node (ref "J1") (pin "18") (pinfunction "18_18") (pintype "passive"))
      (node (ref "U1") (pin "19") (pinfunction "GPIO15/RTC_GPIO15/U0RTS/ADC2_CH4/XTAL_32K_P_19") (pintype "passive"))
    )
    (net (code "38") (name "/GPIO16") (class "Default")
      (node (ref "J1") (pin "19") (pinfunction "19_19") (pintype "passive"))
      (node (ref "U1") (pin "20") (pinfunction "GPIO16/RTC_GPIO16/U0CTS/ADC2_CH5/XTAL_32K_N_20") (pintype "passive"))
    )
    (net (code "39") (name "/GPIO17") (class "Default")
      (node (ref "J1") (pin "20") (pinfunction "20_20") (pintype "passive"))
      (node (ref "U1") (pin "21") (pinfunction "GPIO17/RTC_GPIO17/U1TXD/ADC2_CH6_21") (pintype "passive"))
    )
    (net (code "40") (name "/GPIO18") (class "Default")
      (node (ref "J1") (pin "21") (pinfunction "21_21") (pintype "passive"))
      (node (ref "U1") (pin "22") (pinfunction "GPIO18/RTC_GPIO18/U1RXD/ADC2_CH7/CLK_OUT3_22") (pintype "passive"))
    )
    (net (code "41") (name "/GPIO21") (class "Default")
      (node (ref "J2") (pin "19") (pinfunction "19_19") (pintype "passive"))
      (node (ref "U1") (pin "25") (pinfunction "GPIO21/RTC_GPIO21_25") (pintype "passive"))
    )
    (net (code "42") (name "/GPIO26") (class "Default")
      (node (ref "J2") (pin "18") (pinfunction "18_18") (pintype "passive"))
      (node (ref "U1") (pin "26") (pinfunction "GPIO26/SPICS1_26") (pintype "passive"))
    )
    (net (code "43") (name "/GPIO33") (class "Default")
      (node (ref "J2") (pin "17") (pinfunction "17_17") (pintype "passive"))
      (node (ref "U1") (pin "28") (pinfunction "GPIO33/SPIIO4/FSPIHD/SUBSPIHD_28") (pintype "passive"))
    )
    (net (code "44") (name "/GPIO34") (class "Default")
      (node (ref "J2") (pin "16") (pinfunction "16_16") (pintype "passive"))
      (node (ref "U1") (pin "29") (pinfunction "GPIO34/SPIIO5/FSPICS0/SUBSPICS0_29") (pintype "passive"))
    )
    (net (code "45") (name "/GPIO35") (class "Default")
      (node (ref "J2") (pin "15") (pinfunction "15_15") (pintype "passive"))
      (node (ref "U1") (pin "31") (pinfunction "GPIO35/SPIIO6/FSPID/SUBSPID_31") (pintype "passive"))
    )
    (net (code "46") (name "/GPIO36") (class "Default")
      (node (ref "J2") (pin "14") (pinfunction "14_14") (pintype "passive"))
      (node (ref "U1") (pin "32") (pinfunction "GPIO36/SPIIO7/FSPICLK/SUBSPICLK_32") (pintype "passive"))
    )
    (net (code "47") (name "/GPIO37") (class "Default")
      (node (ref "J2") (pin "13") (pinfunction "13_13") (pintype "passive"))
      (node (ref "U1") (pin "33") (pinfunction "GPIO37/SPIDQS/FSPIQ/SUBSPIQ_33") (pintype "passive"))
    )
    (net (code "48") (name "/GPIO38") (class "Default")
      (node (ref "J2") (pin "12") (pinfunction "12_12") (pintype "passive"))
      (node (ref "U1") (pin "34") (pinfunction "GPIO38/FSPIWP/SUBSPIWP_34") (pintype "passive"))
    )
    (net (code "49") (name "/GPIO39") (class "Default")
      (node (ref "J2") (pin "11") (pinfunction "11_11") (pintype "passive"))
      (node (ref "U1") (pin "35") (pinfunction "MTCK/GPIO39/CLK_OUT3/SUBSPICS1_35") (pintype "passive"))
    )
    (net (code "50") (name "/GPIO40") (class "Default")
      (node (ref "J2") (pin "10") (pinfunction "10_10") (pintype "passive"))
      (node (ref "U1") (pin "36") (pinfunction "MTDO/GPIO40/CLK_OUT2_36") (pintype "passive"))
    )
    (net (code "51") (name "/GPIO41") (class "Default")
      (node (ref "J2") (pin "9") (pinfunction "9_9") (pintype "passive"))
      (node (ref "U1") (pin "37") (pinfunction "MTDI/GPIO41/CLK_OUT1_37") (pintype "passive"))
    )
    (net (code "52") (name "/GPIO42") (class "Default")
      (node (ref "J2") (pin "8") (pinfunction "8_8") (pintype "passive"))
      (node (ref "U1") (pin "38") (pinfunction "MTMS/GPIO42_38") (pintype "passive"))
    )
    (net (code "53") (name "/GPIO45") (class "Default")
      (node (ref "J2") (pin "5") (pinfunction "5_5") (pintype "passive"))
      (node (ref "U1") (pin "41") (pinfunction "GPIO45_41") (pintype "passive"))
    )
    (net (code "54") (name "/GPIO46") (class "Default")
      (node (ref "J2") (pin "4") (pinfunction "4_4") (pintype "passive"))
      (node (ref "U1") (pin "44") (pinfunction "GPIO46_44") (pintype "passive"))
    )
    (net (code "55") (name "/GPIO47") (class "Default")
      (node (ref "J2") (pin "23") (pinfunction "23_23") (pintype "passive"))
      (node (ref "U1") (pin "27") (pinfunction "GPIO47/SPICLK_P_DIFF/SUBSPICLK_P_DIFF_27") (pintype "passive"))
    )
    (net (code "56") (name "/GPIO48") (class "Default")
      (node (ref "J2") (pin "22") (pinfunction "22_22") (pintype "passive"))
      (node (ref "U1") (pin "30") (pinfunction "GPIO48/SPICLK_N_DIFF/SUBSPICLK_N_DIFF_30") (pintype "passive"))
    )
    (net (code "57") (name "/RTS_FTDI") (class "Default")
      (node (ref "Q1") (pin "2") (pinfunction "E_2") (pintype "passive"))
      (node (ref "R22") (pin "2") (pinfunction "2_2") (pintype "passive"))
      (node (ref "U2") (pin "19") (pinfunction "~{RTS}_19") (pintype "passive"))
    )
    (net (code "58") (name "/RXD_FTDI") (class "Default")
      (node (ref "R21") (pin "2") (pinfunction "2_2") (pintype "passive"))
      (node (ref "U2") (pin "1") (pinfunction "RXD_1") (pintype "passive"))
    )
    (net (code "59") (name "/TXD_FTDI") (class "Default")
      (node (ref "R18") (pin "2") (pinfunction "2_2") (pintype "passive"))
      (node (ref "U2") (pin "17") (pinfunction "TXD_17") (pintype "passive"))
    )
    (net (code "60") (name "/U0RXD") (class "Default")
      (node (ref "J2") (pin "6") (pinfunction "6_6") (pintype "passive"))
      (node (ref "R21") (pin "1") (pinfunction "1_1") (pintype "passive"))
      (node (ref "U1") (pin "40") (pinfunction "U0RXD/GPIO44/CLK_OUT2_40") (pintype "passive"))
    )
    (net (code "61") (name "/U0TXD") (class "Default")
      (node (ref "J2") (pin "7") (pinfunction "7_7") (pintype "passive"))
      (node (ref "R18") (pin "1") (pinfunction "1_1") (pintype "passive"))
      (node (ref "U1") (pin "39") (pinfunction "U0TXD/GPIO43/CLK_OUT1_39") (pintype "passive"))
    )
    (net (code "62") (name "/VBUS_SENSE") (class "Default")
      (node (ref "R10") (pin "1") (pinfunction "1_1") (pintype "passive"))
      (node (ref "R13") (pin "2") (pinfunction "2_2") (pintype "passive"))
      (node (ref "U2") (pin "16") (pinfunction "CBUS3_16") (pintype "passive"))
    )
    (net (code "63") (name "GND") (class "Default")
      (node (ref "C1") (pin "2") (pinfunction "2_2") (pintype "passive"))
      (node (ref "C10") (pin "2") (pinfunction "2_2") (pintype "passive"))
      (node (ref "C11") (pin "2") (pinfunction "2_2") (pintype "passive"))
      (node (ref "C12") (pin "2") (pinfunction "2_2") (pintype "passive"))
      (node (ref "C13") (pin "2") (pinfunction "2_2") (pintype "passive"))
      (node (ref "C14") (pin "2") (pinfunction "2_2") (pintype "passive"))
      (node (ref "C15") (pin "2") (pinfunction "2_2") (pintype "passive"))
      (node (ref "C16") (pin "1") (pinfunction "1_1") (pintype "passive"))
      (node (ref "C17") (pin "2") (pinfunction "2_2") (pintype "passive"))
      (node (ref "C2") (pin "2") (pinfunction "2_2") (pintype "passive"))
      (node (ref "C3") (pin "2") (pinfunction "2_2") (pintype "passive"))
      (node (ref "C4") (pin "2") (pinfunction "2_2") (pintype "passive"))
      (node (ref "C5") (pin "2") (pinfunction "2_2") (pintype "passive"))
      (node (ref "C6") (pin "2") (pinfunction "2_2") (pintype "passive"))
      (node (ref "C7") (pin "2") (pinfunction "2_2") (pintype "passive"))
      (node (ref "C8") (pin "2") (pinfunction "2_2") (pintype "passive"))
      (node (ref "C9") (pin "2") (pinfunction "2_2") (pintype "passive"))
      (node (ref "D1") (pin "1") (pinfunction "1_1") (pintype "passive"))
      (node (ref "D3") (pin "1") (pinfunction "1_1") (pintype "passive"))
      (node (ref "D4") (pin "1") (pinfunction "1_1") (pintype "passive"))
      (node (ref "D5") (pin "1") (pinfunction "1_1") (pintype "passive"))
      (node (ref "D6") (pin "1") (pinfunction "1_1") (pintype "passive"))
      (node (ref "D7") (pin "1") (pinfunction "1_1") (pintype "passive"))
      (node (ref "D8") (pin "1") (pinfunction "1_1") (pintype "passive"))
      (node (ref "J1") (pin "1") (pinfunction "1_1") (pintype "passive"))
      (node (ref "J1") (pin "23") (pinfunction "23_23") (pintype "passive"))
      (node (ref "J2") (pin "2") (pinfunction "2_2") (pintype "passive"))
      (node (ref "J2") (pin "24") (pinfunction "24_24") (pintype "passive"))
      (node (ref "J3") (pin "A1B12") (pinfunction "GND_A1B12_A1B12") (pintype "passive"))
      (node (ref "J3") (pin "B1A12") (pinfunction "GND_B1A12_B1A12") (pintype "passive"))
      (node (ref "J3") (pin "S1") (pinfunction "SHIELD_1_S1") (pintype "passive"))
      (node (ref "J3") (pin "S2") (pinfunction "SHIELD_2_S2") (pintype "passive"))
      (node (ref "J3") (pin "S3") (pinfunction "SHIELD_3_S3") (pintype "passive"))
      (node (ref "J3") (pin "S4") (pinfunction "SHIELD_4_S4") (pintype "passive"))
      (node (ref "J4") (pin "A1B12") (pinfunction "GND_A1B12_A1B12") (pintype "passive"))
      (node (ref "J4") (pin "B1A12") (pinfunction "GND_B1A12_B1A12") (pintype "passive"))
      (node (ref "J4") (pin "S1") (pinfunction "SHIELD_1_S1") (pintype "passive"))
      (node (ref "J4") (pin "S2") (pinfunction "SHIELD_2_S2") (pintype "passive"))
      (node (ref "J4") (pin "S3") (pinfunction "SHIELD_3_S3") (pintype "passive"))
      (node (ref "J4") (pin "S4") (pinfunction "SHIELD_4_S4") (pintype "passive"))
      (node (ref "R11") (pin "2") (pinfunction "2_2") (pintype "passive"))
      (node (ref "R12") (pin "2") (pinfunction "2_2") (pintype "passive"))
      (node (ref "R13") (pin "1") (pinfunction "1_1") (pintype "passive"))
      (node (ref "R14") (pin "2") (pinfunction "2_2") (pintype "passive"))
      (node (ref "R15") (pin "2") (pinfunction "2_2") (pintype "passive"))
      (node (ref "R9") (pin "1") (pinfunction "1_1") (pintype "passive"))
      (node (ref "SW1") (pin "3") (pinfunction "3_3") (pintype "passive"))
      (node (ref "SW1") (pin "4") (pinfunction "4_4") (pintype "passive"))
      (node (ref "SW2") (pin "3") (pinfunction "3_3") (pintype "passive"))
      (node (ref "SW2") (pin "4") (pinfunction "4_4") (pintype "passive"))
      (node (ref "U1") (pin "1") (pinfunction "GND_01_1") (pintype "passive"))
      (node (ref "U1") (pin "2") (pinfunction "GND_02_2") (pintype "passive"))
      (node (ref "U1") (pin "42") (pinfunction "GND_42") (pintype "passive"))
      (node (ref "U1") (pin "43") (pinfunction "GND_43") (pintype "passive"))
      (node (ref "U1") (pin "46") (pinfunction "GND_46_46") (pintype "passive"))
      (node (ref "U1") (pin "47") (pinfunction "GND_47_47") (pintype "passive"))
      (node (ref "U1") (pin "48") (pinfunction "GND_48_48") (pintype "passive"))
      (node (ref "U1") (pin "49") (pinfunction "GND_49_49") (pintype "passive"))
      (node (ref "U1") (pin "50") (pinfunction "GND_50_50") (pintype "passive"))
      (node (ref "U1") (pin "51") (pinfunction "GND_51_51") (pintype "passive"))
      (node (ref "U1") (pin "52") (pinfunction "GND_52_52") (pintype "passive"))
      (node (ref "U1") (pin "53") (pinfunction "GND_53_53") (pintype "passive"))
      (node (ref "U1") (pin "54") (pinfunction "GND_54_54") (pintype "passive"))
      (node (ref "U1") (pin "55") (pinfunction "GND_55_55") (pintype "passive"))
      (node (ref "U1") (pin "56") (pinfunction "GND_56_56") (pintype "passive"))
      (node (ref "U1") (pin "57") (pinfunction "GND_57_57") (pintype "passive"))
      (node (ref "U1") (pin "58") (pinfunction "GND_58_58") (pintype "passive"))
      (node (ref "U1") (pin "59") (pinfunction "GND_59_59") (pintype "passive"))
      (node (ref "U1") (pin "60") (pinfunction "GND_60_60") (pintype "passive"))
      (node (ref "U1") (pin "61") (pinfunction "GND_61_61") (pintype "passive"))
      (node (ref "U1") (pin "62") (pinfunction "GND_62_62") (pintype "passive"))
      (node (ref "U1") (pin "63") (pinfunction "GND_63_63") (pintype "passive"))
      (node (ref "U1") (pin "64") (pinfunction "GND_64_64") (pintype "passive"))
      (node (ref "U1") (pin "65") (pinfunction "GND_65_65") (pintype "passive"))
      (node (ref "U1") (pin "66") (pinfunction "GND_66_66") (pintype "passive"))
      (node (ref "U1") (pin "67") (pinfunction "GND_67_67") (pintype "passive"))
      (node (ref "U1") (pin "68") (pinfunction "GND_68_68") (pintype "passive"))
      (node (ref "U1") (pin "69") (pinfunction "GND_69_69") (pintype "passive"))
      (node (ref "U1") (pin "70") (pinfunction "GND_70_70") (pintype "passive"))
      (node (ref "U1") (pin "71") (pinfunction "GND_71_71") (pintype "passive"))
      (node (ref "U1") (pin "72") (pinfunction "GND_72_72") (pintype "passive"))
      (node (ref "U1") (pin "73") (pinfunction "GND_73_73") (pintype "passive"))
      (node (ref "U2") (pin "13") (pinfunction "GND_13") (pintype "passive"))
      (node (ref "U2") (pin "21") (pinfunction "GND_21") (pintype "passive"))
      (node (ref "U2") (pin "3") (pinfunction "GND_3") (pintype "passive"))
      (node (ref "U3") (pin "2") (pinfunction "GND_2") (pintype "power_in"))
      (node (ref "U3") (pin "4") (pinfunction "GND_4") (pintype "power_in"))
    )
    (net (code "64") (name "Net-(D1-Pad2)") (class "Default")
      (node (ref "D1") (pin "2") (pinfunction "2_2") (pintype "passive"))
      (node (ref "R4") (pin "1") (pinfunction "1_1") (pintype "passive"))
    )
    (net (code "65") (name "Net-(D2-Pad2)") (class "Default")
      (node (ref "D2") (pin "2") (pinfunction "2_2") (pintype "passive"))
      (node (ref "R5") (pin "1") (pinfunction "1_1") (pintype "passive"))
    )
    (net (code "66") (name "Net-(J3-CC1)") (class "Default")
      (node (ref "J3") (pin "A5") (pinfunction "CC1_A5") (pintype "passive"))
      (node (ref "R11") (pin "1") (pinfunction "1_1") (pintype "passive"))
    )
    (net (code "67") (name "Net-(J3-CC2)") (class "Default")
      (node (ref "J3") (pin "B5") (pinfunction "CC2_B5") (pintype "passive"))
      (node (ref "R12") (pin "1") (pinfunction "1_1") (pintype "passive"))
    )
    (net (code "68") (name "Net-(J4-CC1)") (class "Default")
      (node (ref "J4") (pin "A5") (pinfunction "CC1_A5") (pintype "passive"))
      (node (ref "R14") (pin "1") (pinfunction "1_1") (pintype "passive"))
    )
    (net (code "69") (name "Net-(J4-CC2)") (class "Default")
      (node (ref "J4") (pin "B5") (pinfunction "CC2_B5") (pintype "passive"))
      (node (ref "R15") (pin "1") (pinfunction "1_1") (pintype "passive"))
    )
    (net (code "70") (name "Net-(Q1-B)") (class "Default")
      (node (ref "Q1") (pin "1") (pinfunction "B_1") (pintype "passive"))
      (node (ref "R16") (pin "1") (pinfunction "1_1") (pintype "passive"))
    )
    (net (code "71") (name "Net-(Q2-B)") (class "Default")
      (node (ref "Q2") (pin "1") (pinfunction "B_1") (pintype "passive"))
      (node (ref "R22") (pin "1") (pinfunction "1_1") (pintype "passive"))
    )
    (net (code "72") (name "Net-(U2-CBUS0)") (class "Default")
      (node (ref "R9") (pin "2") (pinfunction "2_2") (pintype "passive"))
      (node (ref "U2") (pin "15") (pinfunction "CBUS0_15") (pintype "passive"))
    )
    (net (code "73") (name "Net-(U2-~{RESET})") (class "Default")
      (node (ref "C9") (pin "1") (pinfunction "1_1") (pintype "passive"))
      (node (ref "R8") (pin "2") (pinfunction "2_2") (pintype "passive"))
      (node (ref "U2") (pin "11") (pinfunction "~{RESET}_11") (pintype "passive"))
    )
    (net (code "74") (name "unconnected-(J1-Pad24)") (class "Default")
      (node (ref "J1") (pin "24") (pinfunction "24_24") (pintype "passive+no_connect"))
    )
    (net (code "75") (name "unconnected-(J3-SBU1-PadA8)") (class "Default")
      (node (ref "J3") (pin "A8") (pinfunction "SBU1_A8") (pintype "passive+no_connect"))
    )
    (net (code "76") (name "unconnected-(J3-SBU2-PadB8)") (class "Default")
      (node (ref "J3") (pin "B8") (pinfunction "SBU2_B8") (pintype "passive+no_connect"))
    )
    (net (code "77") (name "unconnected-(J4-SBU1-PadA8)") (class "Default")
      (node (ref "J4") (pin "A8") (pinfunction "SBU1_A8") (pintype "passive+no_connect"))
    )
    (net (code "78") (name "unconnected-(J4-SBU2-PadB8)") (class "Default")
      (node (ref "J4") (pin "B8") (pinfunction "SBU2_B8") (pintype "passive+no_connect"))
    )
    (net (code "79") (name "unconnected-(U2-CBUS1-Pad14)") (class "Default")
      (node (ref "U2") (pin "14") (pinfunction "CBUS1_14") (pintype "passive+no_connect"))
    )
    (net (code "80") (name "unconnected-(U2-CBUS2-Pad7)") (class "Default")
      (node (ref "U2") (pin "7") (pinfunction "CBUS2_7") (pintype "passive+no_connect"))
    )
    (net (code "81") (name "unconnected-(U2-~{CTS}-Pad6)") (class "Default")
      (node (ref "U2") (pin "6") (pinfunction "~{CTS}_6") (pintype "passive+no_connect"))
    )
    (net (code "82") (name "unconnected-(U2-~{DCD}-Pad5)") (class "Default")
      (node (ref "U2") (pin "5") (pinfunction "~{DCD}_5") (pintype "passive+no_connect"))
    )
    (net (code "83") (name "unconnected-(U2-~{DSR}-Pad4)") (class "Default")
      (node (ref "U2") (pin "4") (pinfunction "~{DSR}_4") (pintype "passive+no_connect"))
    )
    (net (code "84") (name "unconnected-(U2-~{RI}-Pad2)") (class "Default")
      (node (ref "U2") (pin "2") (pinfunction "~{RI}_2") (pintype "passive+no_connect"))
    )
  )
)
